# ET-UARTPmod.net
KiCad netlist of a schematic drawn in Altium Designer
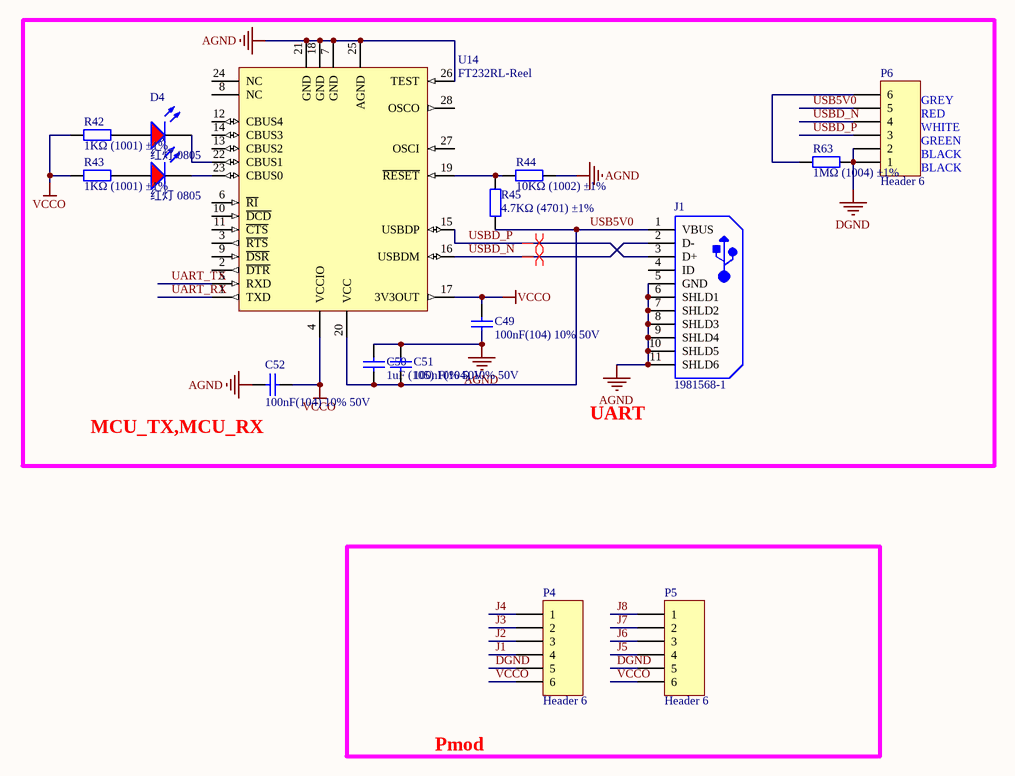
[diagram p0: ET-UARTPmod.SchDoc]

(export (version "E")
  (design (tool "Eeschema 10.0.6"))
  (components
    (comp (ref "C49")
      (value "100nF(104) 10% 50V")
      (footprint "LC-0805_C")
      (description "贴片电容")
      (libsource (lib "Miscellaneous Devices LC") (part "0805 100nF(104) 10% 50V"))
    )
    (comp (ref "C50")
      (value "1uF (105) 10% 50V")
      (footprint "LC-0805_C")
      (description "贴片电容")
      (libsource (lib "Miscellaneous Devices LC") (part "0805 1uF (105) 10% 50V"))
    )
    (comp (ref "C51")
      (value "100nF(104) 10% 50V")
      (footprint "LC-0805_C")
      (description "贴片电容")
      (libsource (lib "Miscellaneous Devices LC") (part "0805 100nF(104) 10% 50V"))
    )
    (comp (ref "C52")
      (value "100nF(104) 10% 50V")
      (footprint "LC-0805_C")
      (description "贴片电容")
      (libsource (lib "Miscellaneous Devices LC") (part "0805 100nF(104) 10% 50V"))
    )
    (comp (ref "D4")
      (value "红灯 0805")
      (footprint "LC-0805_LED_S1")
      (description "发光二极管")
      (libsource (lib "Miscellaneous Devices LC") (part "0805 红灯"))
    )
    (comp (ref "D5")
      (value "红灯 0805")
      (footprint "LC-0805_LED_S1")
      (description "发光二极管")
      (libsource (lib "Miscellaneous Devices LC") (part "0805 红灯"))
    )
    (comp (ref "J1")
      (value "1981568-1")
      (footprint "TECO-1981568-5_V")
      (description "Micro USB Receptacle Standard Type B Assy, 5-Pin SMD, RoHS, Tape and Reel")
      (libsource (lib "TE Audio, Video and High Speed Serial Connectors") (part "1981568-1"))
    )
    (comp (ref "P4")
      (value "Header 6")
      (footprint "HDR1X6")
      (description "Header, 6-Pin")
      (fields (field (name "PUBLISHER") "Altium Limited"))
      (libsource (lib "") (part "Header 6_1"))
    )
    (comp (ref "P5")
      (value "Header 6")
      (footprint "HDR1X6")
      (description "Header, 6-Pin")
      (fields (field (name "PUBLISHER") "Altium Limited"))
      (libsource (lib "") (part "Header 6_1"))
    )
    (comp (ref "P6")
      (value "Header 6")
      (footprint "HDR1X6")
      (description "Header, 6-Pin")
      (fields (field (name "PUBLISHER") "Altium Limited"))
      (libsource (lib "Miscellaneous Connectors") (part "Header 6"))
    )
    (comp (ref "R42")
      (value "1KΩ (1001) ±1%")
      (footprint "LC-0805_R")
      (description "贴片电阻")
      (libsource (lib "Miscellaneous Devices LC") (part "0805 1KΩ (1001) 1%"))
    )
    (comp (ref "R43")
      (value "1KΩ (1001) ±1%")
      (footprint "LC-0805_R")
      (description "贴片电阻")
      (libsource (lib "Miscellaneous Devices LC") (part "0805 1KΩ (1001) 1%"))
    )
    (comp (ref "R44")
      (value "10KΩ (1002) ±1%")
      (footprint "LC-0805_R")
      (description "贴片电阻")
      (libsource (lib "Miscellaneous Devices LC") (part "0805 10KΩ (1002) 1%"))
    )
    (comp (ref "R45")
      (value "4.7KΩ (4701) ±1%")
      (footprint "LC-0805_R")
      (description "贴片电阻")
      (libsource (lib "Miscellaneous Devices LC") (part "0805 4.7KΩ (4701) 1%"))
    )
    (comp (ref "R63")
      (value "1MΩ (1004) ±1%")
      (footprint "LC-0805_R")
      (description "贴片电阻")
      (libsource (lib "Miscellaneous Devices LC") (part "0805 1MΩ (1004) 1%"))
    )
    (comp (ref "U14")
      (value "FT232RL-Reel")
      (footprint "SSOP-28_N")
      (description "USB UART Asynchronous Serial Data Transfer Chip, SSOP-28, Tape and Reel")
      (fields (field (name "PUBLISHER") "Altium Limited"))
      (libsource (lib "FTDI Communication UART") (part "FT232RL-Reel"))
    )
  )
  (nets
    (net (code "4") (name "/J1") (class "Default")
      (node (ref "P4") (pin "4") (pinfunction "4_4") (pintype "passive"))
    )
    (net (code "5") (name "/J2") (class "Default")
      (node (ref "P4") (pin "3") (pinfunction "3_3") (pintype "passive"))
    )
    (net (code "6") (name "/J3") (class "Default")
      (node (ref "P4") (pin "2") (pinfunction "2_2") (pintype "passive"))
    )
    (net (code "7") (name "/J4") (class "Default")
      (node (ref "P4") (pin "1") (pinfunction "1_1") (pintype "passive"))
    )
    (net (code "8") (name "/J5") (class "Default")
      (node (ref "P5") (pin "4") (pinfunction "4_4") (pintype "passive"))
    )
    (net (code "9") (name "/J6") (class "Default")
      (node (ref "P5") (pin "3") (pinfunction "3_3") (pintype "passive"))
    )
    (net (code "10") (name "/J7") (class "Default")
      (node (ref "P5") (pin "2") (pinfunction "2_2") (pintype "passive"))
    )
    (net (code "11") (name "/J8") (class "Default")
      (node (ref "P5") (pin "1") (pinfunction "1_1") (pintype "passive"))
    )
    (net (code "13") (name "/UART_RX") (class "Default")
      (node (ref "U14") (pin "1") (pinfunction "TXD_1") (pintype "output"))
    )
    (net (code "14") (name "/UART_TX") (class "Default")
      (node (ref "U14") (pin "5") (pinfunction "RXD_5") (pintype "input"))
    )
    (net (code "15") (name "/USB5V0") (class "Default")
      (node (ref "C50") (pin "2") (pinfunction "2_2") (pintype "passive"))
      (node (ref "C51") (pin "2") (pinfunction "2_2") (pintype "passive"))
      (node (ref "J1") (pin "1") (pinfunction "VBUS_1") (pintype "passive"))
      (node (ref "P6") (pin "5") (pinfunction "5_5") (pintype "passive"))
      (node (ref "R45") (pin "2") (pinfunction "2_2") (pintype "passive"))
      (node (ref "U14") (pin "20") (pinfunction "VCC_20") (pintype "power_in"))
    )
    (net (code "16") (name "/USBD_N") (class "Default")
      (node (ref "J1") (pin "2") (pinfunction "D-_2") (pintype "passive"))
      (node (ref "P6") (pin "4") (pinfunction "4_4") (pintype "passive"))
      (node (ref "U14") (pin "16") (pinfunction "USBDM_16") (pintype "bidirectional"))
    )
    (net (code "17") (name "/USBD_P") (class "Default")
      (node (ref "J1") (pin "3") (pinfunction "D+_3") (pintype "passive"))
      (node (ref "P6") (pin "3") (pinfunction "3_3") (pintype "passive"))
      (node (ref "U14") (pin "15") (pinfunction "USBDP_15") (pintype "bidirectional"))
    )
    (net (code "19") (name "AGND") (class "Default")
      (node (ref "C49") (pin "2") (pinfunction "2_2") (pintype "passive"))
      (node (ref "C50") (pin "1") (pinfunction "1_1") (pintype "passive"))
      (node (ref "C51") (pin "1") (pinfunction "1_1") (pintype "passive"))
      (node (ref "C52") (pin "1") (pinfunction "1_1") (pintype "passive"))
      (node (ref "J1") (pin "10") (pinfunction "SHLD5_10") (pintype "passive"))
      (node (ref "J1") (pin "11") (pinfunction "SHLD6_11") (pintype "passive"))
      (node (ref "J1") (pin "5") (pinfunction "GND_5") (pintype "passive"))
      (node (ref "J1") (pin "6") (pinfunction "SHLD1_6") (pintype "passive"))
      (node (ref "J1") (pin "7") (pinfunction "SHLD2_7") (pintype "passive"))
      (node (ref "J1") (pin "8") (pinfunction "SHLD3_8") (pintype "passive"))
      (node (ref "J1") (pin "9") (pinfunction "SHLD4_9") (pintype "passive"))
      (node (ref "R44") (pin "1") (pinfunction "1_1") (pintype "passive"))
      (node (ref "U14") (pin "18") (pinfunction "GND_18") (pintype "power_in"))
      (node (ref "U14") (pin "21") (pinfunction "GND_21") (pintype "power_in"))
      (node (ref "U14") (pin "25") (pinfunction "AGND_25") (pintype "power_in"))
      (node (ref "U14") (pin "26") (pinfunction "TEST_26") (pintype "input"))
      (node (ref "U14") (pin "7") (pinfunction "GND_7") (pintype "power_in"))
    )
    (net (code "20") (name "DGND") (class "Default")
      (node (ref "P4") (pin "5") (pinfunction "5_5") (pintype "passive"))
      (node (ref "P5") (pin "5") (pinfunction "5_5") (pintype "passive"))
      (node (ref "P6") (pin "1") (pinfunction "1_1") (pintype "passive"))
      (node (ref "P6") (pin "2") (pinfunction "2_2") (pintype "passive"))
      (node (ref "R63") (pin "2") (pinfunction "2_2") (pintype "passive"))
    )
    (net (code "21") (name "Net-(D4-PadA)") (class "Default")
      (node (ref "D4") (pin "A") (pinfunction "A_A") (pintype "passive"))
      (node (ref "R42") (pin "1") (pinfunction "1_1") (pintype "passive"))
    )
    (net (code "22") (name "Net-(D5-PadA)") (class "Default")
      (node (ref "D5") (pin "A") (pinfunction "A_A") (pintype "passive"))
      (node (ref "R43") (pin "1") (pinfunction "1_1") (pintype "passive"))
    )
    (net (code "23") (name "Net-(P6-Pad6)") (class "Default")
      (node (ref "P6") (pin "6") (pinfunction "6_6") (pintype "passive"))
      (node (ref "R63") (pin "1") (pinfunction "1_1") (pintype "passive"))
    )
    (net (code "24") (name "Net-(U14-CBUS0)") (class "Default")
      (node (ref "D5") (pin "K") (pinfunction "K_K") (pintype "passive"))
      (node (ref "U14") (pin "23") (pinfunction "CBUS0_23") (pintype "bidirectional"))
    )
    (net (code "25") (name "Net-(U14-CBUS1)") (class "Default")
      (node (ref "D4") (pin "K") (pinfunction "K_K") (pintype "passive"))
      (node (ref "U14") (pin "22") (pinfunction "CBUS1_22") (pintype "bidirectional"))
    )
    (net (code "26") (name "Net-(U14-~{RESET})") (class "Default")
      (node (ref "R44") (pin "2") (pinfunction "2_2") (pintype "passive"))
      (node (ref "R45") (pin "1") (pinfunction "1_1") (pintype "passive"))
      (node (ref "U14") (pin "19") (pinfunction "~{RESET}_19") (pintype "input"))
    )
    (net (code "27") (name "VCCO") (class "Default")
      (node (ref "C49") (pin "1") (pinfunction "1_1") (pintype "passive"))
      (node (ref "C52") (pin "2") (pinfunction "2_2") (pintype "passive"))
      (node (ref "P4") (pin "6") (pinfunction "6_6") (pintype "passive"))
      (node (ref "P5") (pin "6") (pinfunction "6_6") (pintype "passive"))
      (node (ref "R42") (pin "2") (pinfunction "2_2") (pintype "passive"))
      (node (ref "R43") (pin "2") (pinfunction "2_2") (pintype "passive"))
      (node (ref "U14") (pin "17") (pinfunction "3V3OUT_17") (pintype "output"))
      (node (ref "U14") (pin "4") (pinfunction "VCCIO_4") (pintype "power_in"))
    )
    (net (code "28") (name "unconnected-(J1-ID-Pad4)") (class "Default")
      (node (ref "J1") (pin "4") (pinfunction "ID_4") (pintype "passive"))
    )
    (net (code "29") (name "unconnected-(U14-CBUS2-Pad13)") (class "Default")
      (node (ref "U14") (pin "13") (pinfunction "CBUS2_13") (pintype "bidirectional"))
    )
    (net (code "30") (name "unconnected-(U14-CBUS3-Pad14)") (class "Default")
      (node (ref "U14") (pin "14") (pinfunction "CBUS3_14") (pintype "bidirectional"))
    )
    (net (code "31") (name "unconnected-(U14-CBUS4-Pad12)") (class "Default")
      (node (ref "U14") (pin "12") (pinfunction "CBUS4_12") (pintype "bidirectional"))
    )
    (net (code "32") (name "unconnected-(U14-NC-Pad8)") (class "Default")
      (node (ref "U14") (pin "8") (pinfunction "NC_8") (pintype "passive"))
    )
    (net (code "33") (name "unconnected-(U14-NC-Pad24)") (class "Default")
      (node (ref "U14") (pin "24") (pinfunction "NC_24") (pintype "passive"))
    )
    (net (code "34") (name "unconnected-(U14-OSCI-Pad27)") (class "Default")
      (node (ref "U14") (pin "27") (pinfunction "OSCI_27") (pintype "input"))
    )
    (net (code "35") (name "unconnected-(U14-OSCO-Pad28)") (class "Default")
      (node (ref "U14") (pin "28") (pinfunction "OSCO_28") (pintype "output"))
    )
    (net (code "36") (name "unconnected-(U14-~{CTS}-Pad11)") (class "Default")
      (node (ref "U14") (pin "11") (pinfunction "~{CTS}_11") (pintype "input"))
    )
    (net (code "37") (name "unconnected-(U14-~{DCD}-Pad10)") (class "Default")
      (node (ref "U14") (pin "10") (pinfunction "~{DCD}_10") (pintype "input"))
    )
    (net (code "38") (name "unconnected-(U14-~{DSR}-Pad9)") (class "Default")
      (node (ref "U14") (pin "9") (pinfunction "~{DSR}_9") (pintype "input"))
    )
    (net (code "39") (name "unconnected-(U14-~{DTR}-Pad2)") (class "Default")
      (node (ref "U14") (pin "2") (pinfunction "~{DTR}_2") (pintype "output"))
    )
    (net (code "40") (name "unconnected-(U14-~{RI}-Pad6)") (class "Default")
      (node (ref "U14") (pin "6") (pinfunction "~{RI}_6") (pintype "input"))
    )
    (net (code "41") (name "unconnected-(U14-~{RTS}-Pad3)") (class "Default")
      (node (ref "U14") (pin "3") (pinfunction "~{RTS}_3") (pintype "output"))
    )
  )
)
